# Sheet2.net
KiCad netlist of a schematic drawn in Altium Designer
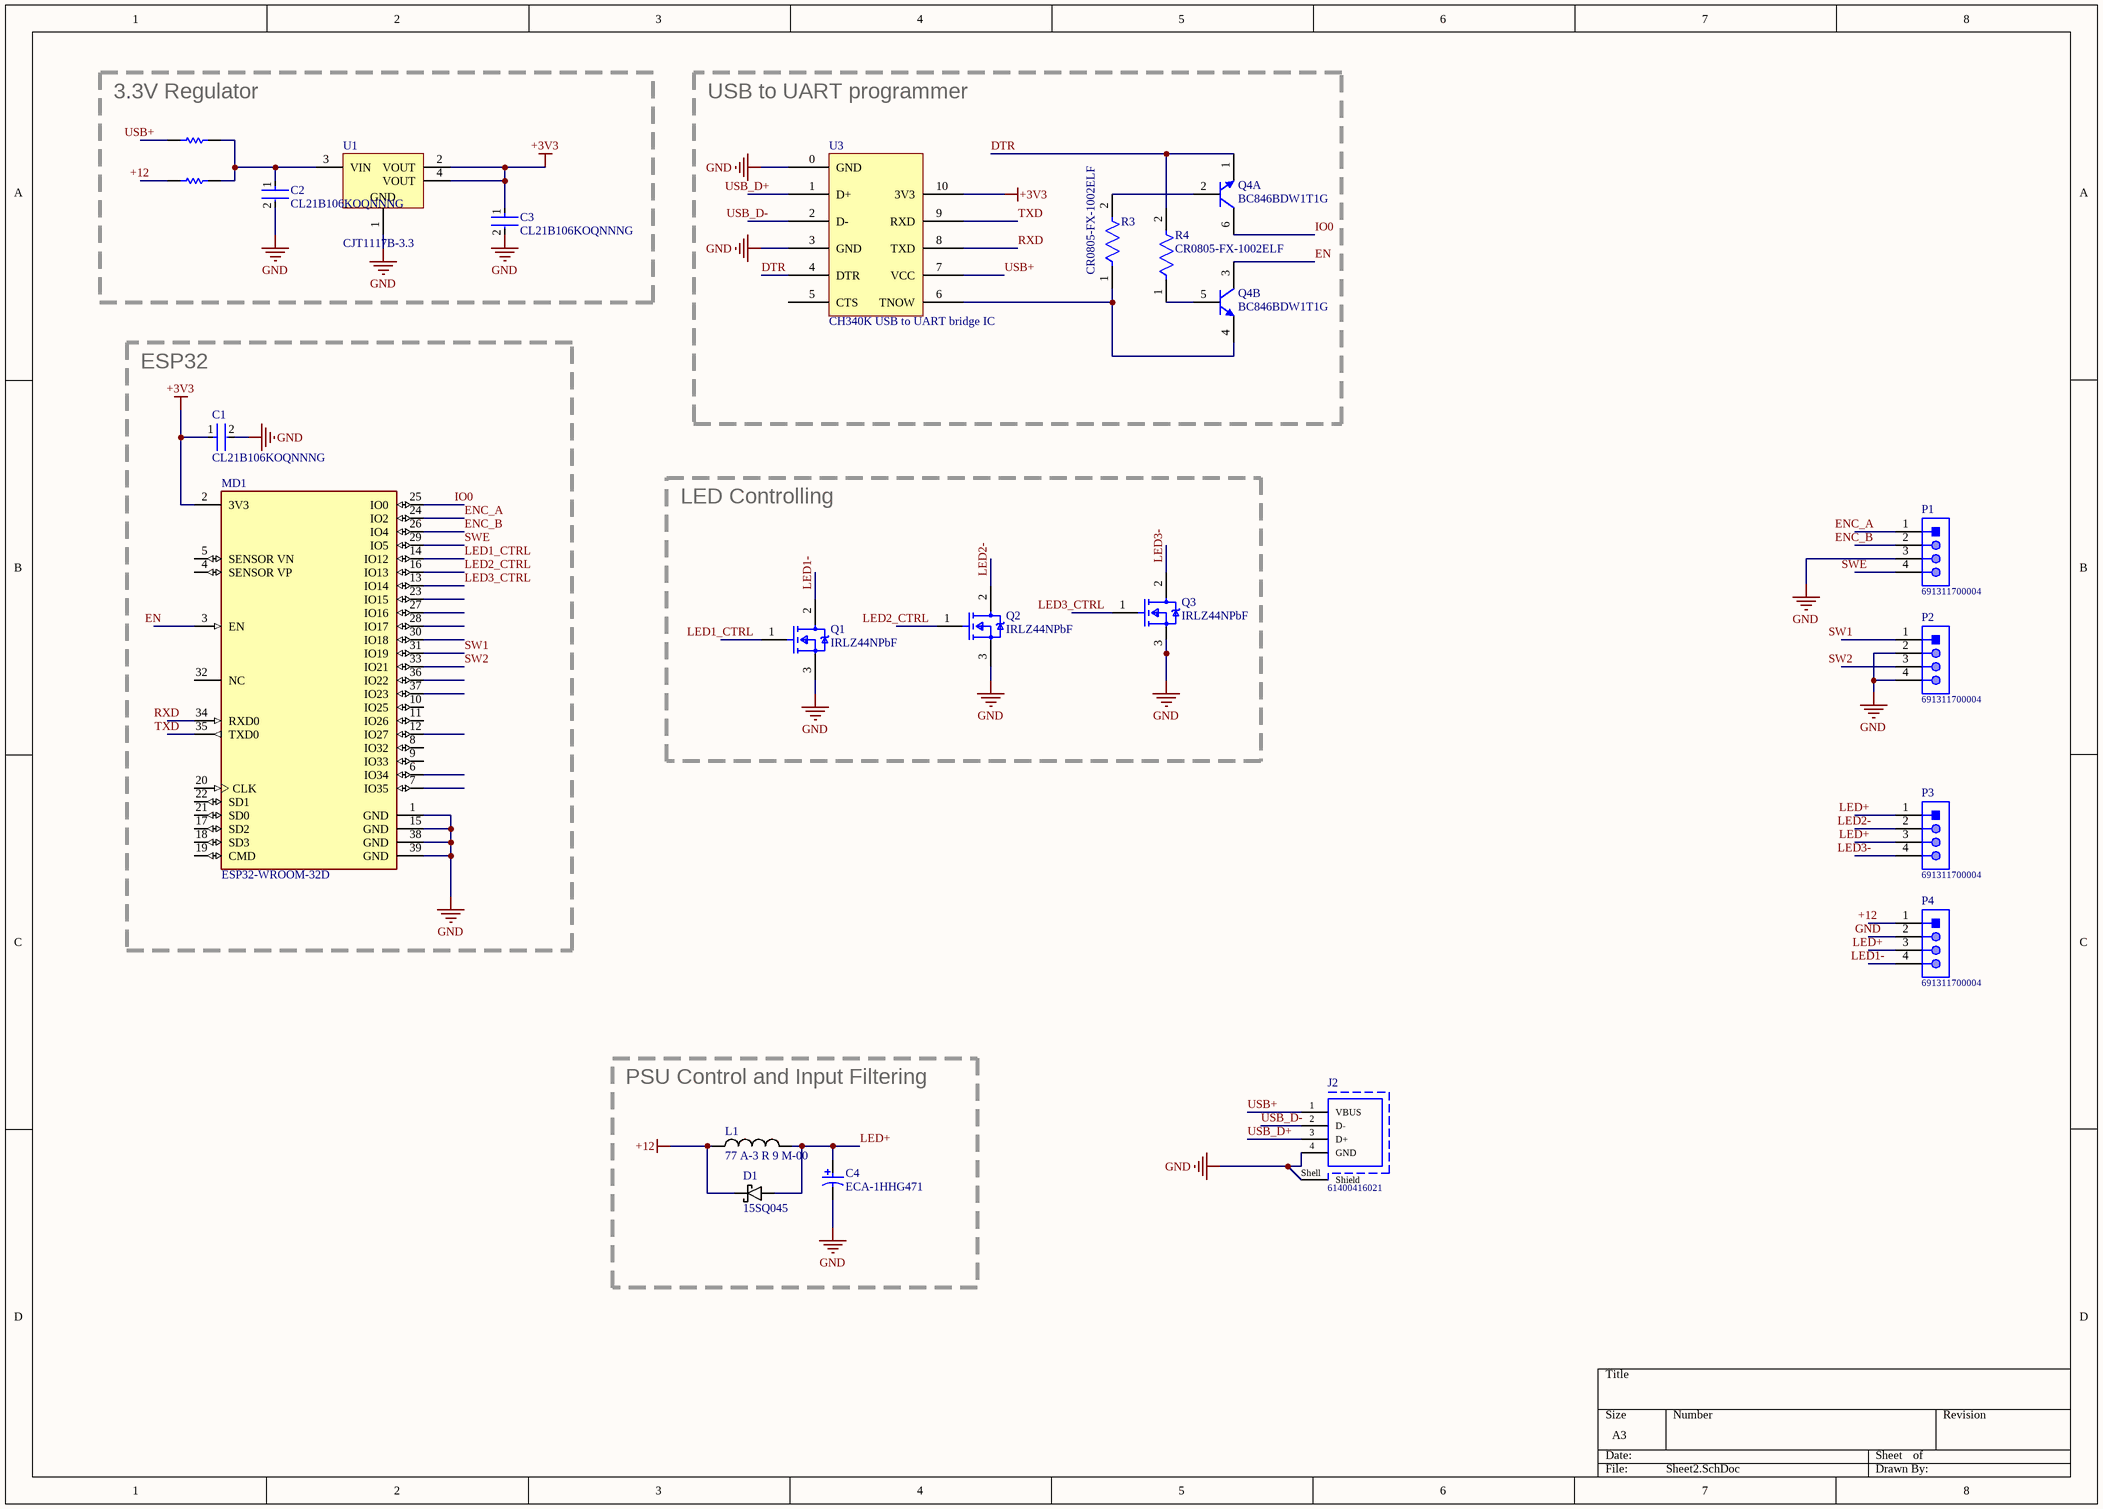
[diagram p0: Sheet2.SchDoc]

(export (version "E")
  (design (tool "Eeschema 10.0.6"))
  (components
    (comp (ref "C1")
      (value "CL21B106KOQNNNG")
      (footprint "FP-CL21B106KOQNNNG-MFG")
      (description "CAP CER 10UF 16V X7R 0805")
      (fields
        (field (name "TOLERANCE") "10%")
        (field (name "OCTOPART") "https://octopart.com/cl21b106koqnnng-samsung-19995691")
      )
      (libsource (lib "Altium Content Vault") (part "b4654b650e69147ec39a6b967a45e02"))
    )
    (comp (ref "C2")
      (value "CL21B106KOQNNNG")
      (footprint "FP-CL21B106KOQNNNG-MFG")
      (description "CAP CER 10UF 16V X7R 0805")
      (fields
        (field (name "TOLERANCE") "10%")
        (field (name "OCTOPART") "https://octopart.com/cl21b106koqnnng-samsung-19995691")
      )
      (libsource (lib "Altium Content Vault") (part "b4654b650e69147ec39a6b967a45e02"))
    )
    (comp (ref "C3")
      (value "CL21B106KOQNNNG")
      (footprint "FP-CL21B106KOQNNNG-MFG")
      (description "CAP CER 10UF 16V X7R 0805")
      (fields
        (field (name "TOLERANCE") "10%")
        (field (name "OCTOPART") "https://octopart.com/cl21b106koqnnng-samsung-19995691")
      )
      (libsource (lib "Altium Content Vault") (part "b4654b650e69147ec39a6b967a45e02"))
    )
    (comp (ref "C4")
      (value "ECA-1HHG471")
      (footprint "PNSC-CAP-10x20-P2")
      (description "Aluminum Electrolytic Capacitor, 470 uF, +/- 20%, 50 V, -55 to 105 degC, 2-Pin THD, RoHS, Bulk")
      (fields (field (name "MANUFACTURER") "Panasonic"))
      (libsource (lib "Altium Content Vault") (part "CAP-P-2"))
    )
    (comp (ref "D1")
      (value "15SQ045")
      (footprint "Shottky Diode")
      (description "Diotec 15SQ045")
      (fields (field (name "VOLTAGE") "45V"))
      (libsource (lib "Schlib1") (part "15SQ045"))
    )
    (comp (ref "J2")
      (value "61400416021")
      (footprint "61400416021")
      (description "USB 2.0 Type A Receptacle WR-COM, Horizontal, THT")
      (fields (field (name "MANUFACTURER") "Wurth Elektronik") (field (name "PUBLISHER") "WurthElektronik"))
      (libsource (lib "Altium Content Vault") (part "WE-USB-4-1SHLD"))
    )
    (comp (ref "L1")
      (value "77 A-3 R 9 M-00")
      (footprint "FIlter Inductor")
      (description "Fastron 77 A-3 R 9 M-00")
      (fields (field (name "TOLERANCE") "+-20%"))
      (libsource (lib "Schlib1") (part "77 A-3 R 9 M-00"))
    )
    (comp (ref "MD1")
      (value "ESP32-WROOM-32D")
      (footprint "FP-ESP32-WROOM-32D-MFG")
      (description "WIFI MODULE 32MBITS SPI FLASH")
      (fields
        (field (name "OCTOPART") "https://octopart.com/esp32-wroom-32d-espressif+systems-91040050")
        (field (name "MANUFACTURER") "Espressif Systems")
      )
      (libsource (lib "Altium Content Vault") (part "a031a76f8c27026a7a7f4657ff233a3"))
    )
    (comp (ref "P1")
      (value "691311700004")
      (footprint "691311700004")
      (description "Serie 3117 - 5.00mm Open Vertical PCB Header WR-TBL, 4 pin, LCSC: DB128V-5.08-4P-GN-S")
      (fields (field (name "MANUFACTURER") "Wurth Elektronik") (field (name "PUBLISHER") "WurthElektronik"))
      (libsource (lib "Altium Content Vault") (part "WE-CN-1P-M-R4"))
    )
    (comp (ref "P2")
      (value "691311700004")
      (footprint "691311700004")
      (description "Serie 3117 - 5.00mm Open Vertical PCB Header WR-TBL, 4 pin, LCSC: DB128V-5.08-4P-GN-S")
      (fields (field (name "MANUFACTURER") "Wurth Elektronik") (field (name "PUBLISHER") "WurthElektronik"))
      (libsource (lib "Altium Content Vault") (part "WE-CN-1P-M-R4"))
    )
    (comp (ref "P3")
      (value "691311700004")
      (footprint "691311700004")
      (description "Serie 3117 - 5.00mm Open Vertical PCB Header WR-TBL, 4 pin, LCSC: DB128V-5.08-4P-GN-S")
      (fields (field (name "MANUFACTURER") "Wurth Elektronik") (field (name "PUBLISHER") "WurthElektronik"))
      (libsource (lib "Altium Content Vault") (part "WE-CN-1P-M-R4"))
    )
    (comp (ref "P4")
      (value "691311700004")
      (footprint "691311700004")
      (description "Serie 3117 - 5.00mm Open Vertical PCB Header WR-TBL, 4 pin, LCSC: DB128V-5.08-4P-GN-S")
      (fields (field (name "MANUFACTURER") "Wurth Elektronik") (field (name "PUBLISHER") "WurthElektronik"))
      (libsource (lib "Altium Content Vault") (part "WE-CN-1P-M-R4"))
    )
    (comp (ref "Q1")
      (value "IRLZ44NPbF")
      (footprint "FP-PG-TO220-3-MFG")
      (description "MOSFET N-CH 55V 47A TO220AB")
      (libsource (lib "Altium Content Vault") (part "b09f7f152735e370c1ea22a33fa83d6"))
    )
    (comp (ref "Q2")
      (value "IRLZ44NPbF")
      (footprint "FP-PG-TO220-3-MFG")
      (description "MOSFET N-CH 55V 47A TO220AB")
      (libsource (lib "Altium Content Vault") (part "b09f7f152735e370c1ea22a33fa83d6"))
    )
    (comp (ref "Q3")
      (value "IRLZ44NPbF")
      (footprint "FP-PG-TO220-3-MFG")
      (description "MOSFET N-CH 55V 47A TO220AB")
      (libsource (lib "Altium Content Vault") (part "b09f7f152735e370c1ea22a33fa83d6"))
    )
    (comp (ref "Q4")
      (value "BC846BDW1T1G")
      (footprint "ONSC-SOT-363-6-419B-02_W_V")
      (description "Dual General Purpose Transistors, NPN, 6-Pin SOT-363, Pb-Free, Tape and Reel")
      (fields (field (name "MANUFACTURER") "On Semiconductor"))
      (libsource (lib "Altium Content Vault") (part "ONSC-NPN_NPN-6_F"))
    )
    (comp (ref "R1")
      (value "RC0603JR-070RL")
      (footprint "RESC1608X55X25ML10T15")
      (description "Chip Resistor, 0 Ohm, +/- 5%, 0.1 W, -55 to 155 degC, 0603 (1608 Metric), RoHS, Tape and Reel")
      (fields (field (name "TOLERANCE") "5%") (field (name "MANUFACTURER") "Yageo"))
      (libsource (lib "Altium Content Vault") (part "RES-2"))
    )
    (comp (ref "R2")
      (value "RC0603JR-070RL")
      (footprint "RESC1608X55X25ML10T15")
      (description "Chip Resistor, 0 Ohm, +/- 5%, 0.1 W, -55 to 155 degC, 0603 (1608 Metric), RoHS, Tape and Reel")
      (fields (field (name "TOLERANCE") "5%") (field (name "MANUFACTURER") "Yageo"))
      (libsource (lib "Altium Content Vault") (part "RES-2"))
    )
    (comp (ref "R3")
      (value "CR0805-FX-1002ELF")
      (footprint "FP-CR0805-IPC_A")
      (description "Thick Film Chip Resistors 0805 10kΩ 0.125W 1% 100ppm/°C")
      (fields (field (name "TOLERANCE") "1%"))
      (libsource (lib "Altium Content Vault") (part "1029c3af85768c4190bb7ad29bc67b5"))
    )
    (comp (ref "R4")
      (value "CR0805-FX-1002ELF")
      (footprint "FP-CR0805-IPC_A")
      (description "Thick Film Chip Resistors 0805 10kΩ 0.125W 1% 100ppm/°C")
      (fields (field (name "TOLERANCE") "1%"))
      (libsource (lib "Altium Content Vault") (part "1029c3af85768c4190bb7ad29bc67b5"))
    )
    (comp (ref "U1")
      (value "CJT1117B-3.3")
      (footprint "DCY0004A_L")
      (libsource (lib "Altium Content Vault") (part "TI-REG1117-XXXX"))
    )
    (comp (ref "U3")
      (value "CH340K USB to UART bridge IC")
      (footprint "CH340K footprint")
      (libsource (lib "Schlib1") (part "CH340K"))
    )
  )
  (nets
    (net (code "1") (name "+3V3") (class "Default")
      (node (ref "C1") (pin "1") (pinfunction "1_1") (pintype "passive"))
      (node (ref "C3") (pin "1") (pinfunction "1_1") (pintype "passive"))
      (node (ref "MD1") (pin "2") (pinfunction "3V3_2") (pintype "power_in"))
      (node (ref "U1") (pin "2") (pinfunction "VOUT_2") (pintype "power_in"))
      (node (ref "U1") (pin "4") (pinfunction "VOUT_4") (pintype "power_in"))
      (node (ref "U3") (pin "10") (pinfunction "3V3_10") (pintype "passive"))
    )
    (net (code "2") (name "+12") (class "Default")
      (node (ref "D1") (pin "2") (pinfunction "2_2") (pintype "passive"))
      (node (ref "L1") (pin "1") (pinfunction "1_1") (pintype "passive"))
      (node (ref "P4") (pin "1") (pinfunction "1_1") (pintype "passive"))
      (node (ref "R2") (pin "1") (pinfunction "1_1") (pintype "passive"))
    )
    (net (code "3") (name "/DTR") (class "Default")
      (node (ref "Q4") (pin "1") (pinfunction "E_1") (pintype "passive"))
      (node (ref "R4") (pin "2") (pinfunction "2_2") (pintype "passive"))
      (node (ref "U3") (pin "4") (pinfunction "DTR_4") (pintype "passive"))
    )
    (net (code "4") (name "/EN") (class "Default")
      (node (ref "MD1") (pin "3") (pinfunction "EN_3") (pintype "input"))
      (node (ref "Q4") (pin "3") (pinfunction "C_3") (pintype "passive"))
    )
    (net (code "5") (name "/ENC_A") (class "Default")
      (node (ref "MD1") (pin "24") (pinfunction "IO2_24") (pintype "bidirectional"))
      (node (ref "P1") (pin "1") (pinfunction "1_1") (pintype "passive"))
    )
    (net (code "6") (name "/ENC_B") (class "Default")
      (node (ref "MD1") (pin "26") (pinfunction "IO4_26") (pintype "bidirectional"))
      (node (ref "P1") (pin "2") (pinfunction "2_2") (pintype "passive"))
    )
    (net (code "7") (name "/IO0") (class "Default")
      (node (ref "MD1") (pin "25") (pinfunction "IO0_25") (pintype "bidirectional"))
      (node (ref "Q4") (pin "6") (pinfunction "C_6") (pintype "passive"))
    )
    (net (code "8") (name "/LED+") (class "Default")
      (node (ref "C4") (pin "1") (pinfunction "1_1") (pintype "passive"))
      (node (ref "D1") (pin "1") (pinfunction "1_1") (pintype "passive"))
      (node (ref "L1") (pin "2") (pinfunction "2_2") (pintype "passive"))
      (node (ref "P3") (pin "1") (pinfunction "1_1") (pintype "passive"))
      (node (ref "P3") (pin "3") (pinfunction "3_3") (pintype "passive"))
      (node (ref "P4") (pin "3") (pinfunction "3_3") (pintype "passive"))
    )
    (net (code "9") (name "/LED1-") (class "Default")
      (node (ref "P4") (pin "4") (pinfunction "4_4") (pintype "passive"))
      (node (ref "Q1") (pin "2") (pinfunction "D_2") (pintype "passive"))
    )
    (net (code "10") (name "/LED1_CTRL") (class "Default")
      (node (ref "MD1") (pin "14") (pinfunction "IO12_14") (pintype "bidirectional"))
      (node (ref "Q1") (pin "1") (pinfunction "G_1") (pintype "passive"))
    )
    (net (code "11") (name "/LED2-") (class "Default")
      (node (ref "P3") (pin "2") (pinfunction "2_2") (pintype "passive"))
      (node (ref "Q2") (pin "2") (pinfunction "D_2") (pintype "passive"))
    )
    (net (code "12") (name "/LED2_CTRL") (class "Default")
      (node (ref "MD1") (pin "16") (pinfunction "IO13_16") (pintype "bidirectional"))
      (node (ref "Q2") (pin "1") (pinfunction "G_1") (pintype "passive"))
    )
    (net (code "13") (name "/LED3-") (class "Default")
      (node (ref "P3") (pin "4") (pinfunction "4_4") (pintype "passive"))
      (node (ref "Q3") (pin "2") (pinfunction "D_2") (pintype "passive"))
    )
    (net (code "14") (name "/LED3_CTRL") (class "Default")
      (node (ref "MD1") (pin "13") (pinfunction "IO14_13") (pintype "bidirectional"))
      (node (ref "Q3") (pin "1") (pinfunction "G_1") (pintype "passive"))
    )
    (net (code "15") (name "/RXD") (class "Default")
      (node (ref "MD1") (pin "34") (pinfunction "RXD0_34") (pintype "input"))
      (node (ref "U3") (pin "8") (pinfunction "TXD_8") (pintype "passive"))
    )
    (net (code "16") (name "/SW1") (class "Default")
      (node (ref "MD1") (pin "31") (pinfunction "IO19_31") (pintype "bidirectional"))
      (node (ref "P2") (pin "1") (pinfunction "1_1") (pintype "passive"))
    )
    (net (code "17") (name "/SW2") (class "Default")
      (node (ref "MD1") (pin "33") (pinfunction "IO21_33") (pintype "bidirectional"))
      (node (ref "P2") (pin "3") (pinfunction "3_3") (pintype "passive"))
    )
    (net (code "18") (name "/SWE") (class "Default")
      (node (ref "MD1") (pin "29") (pinfunction "IO5_29") (pintype "bidirectional"))
      (node (ref "P1") (pin "4") (pinfunction "4_4") (pintype "passive"))
    )
    (net (code "19") (name "/TXD") (class "Default")
      (node (ref "MD1") (pin "35") (pinfunction "TXD0_35") (pintype "output"))
      (node (ref "U3") (pin "9") (pinfunction "RXD_9") (pintype "passive"))
    )
    (net (code "20") (name "/USB+") (class "Default")
      (node (ref "J2") (pin "1") (pinfunction "VBUS_1") (pintype "passive"))
      (node (ref "R1") (pin "1") (pinfunction "1_1") (pintype "passive"))
      (node (ref "U3") (pin "7") (pinfunction "VCC_7") (pintype "passive"))
    )
    (net (code "21") (name "/USB_D+") (class "Default")
      (node (ref "J2") (pin "3") (pinfunction "D+_3") (pintype "passive"))
      (node (ref "U3") (pin "1") (pinfunction "D+_1") (pintype "passive"))
    )
    (net (code "22") (name "/USB_D-") (class "Default")
      (node (ref "J2") (pin "2") (pinfunction "D-_2") (pintype "passive"))
      (node (ref "U3") (pin "2") (pinfunction "D-_2") (pintype "passive"))
    )
    (net (code "23") (name "GND") (class "Default")
      (node (ref "C1") (pin "2") (pinfunction "2_2") (pintype "passive"))
      (node (ref "C2") (pin "2") (pinfunction "2_2") (pintype "passive"))
      (node (ref "C3") (pin "2") (pinfunction "2_2") (pintype "passive"))
      (node (ref "C4") (pin "2") (pinfunction "2_2") (pintype "passive"))
      (node (ref "J2") (pin "4") (pinfunction "GND_4") (pintype "passive"))
      (node (ref "J2") (pin "Shell") (pinfunction "Shield_Shell") (pintype "passive"))
      (node (ref "MD1") (pin "1") (pinfunction "GND_1") (pintype "power_in"))
      (node (ref "MD1") (pin "15") (pinfunction "GND_15") (pintype "power_in"))
      (node (ref "MD1") (pin "38") (pinfunction "GND_38") (pintype "power_in"))
      (node (ref "MD1") (pin "39") (pinfunction "GND_39") (pintype "power_in"))
      (node (ref "P1") (pin "3") (pinfunction "3_3") (pintype "passive"))
      (node (ref "P2") (pin "2") (pinfunction "2_2") (pintype "passive"))
      (node (ref "P2") (pin "4") (pinfunction "4_4") (pintype "passive"))
      (node (ref "P4") (pin "2") (pinfunction "2_2") (pintype "passive"))
      (node (ref "Q1") (pin "3") (pinfunction "S_3") (pintype "passive"))
      (node (ref "Q2") (pin "3") (pinfunction "S_3") (pintype "passive"))
      (node (ref "Q3") (pin "3") (pinfunction "S_3") (pintype "passive"))
      (node (ref "U1") (pin "1") (pinfunction "GND_1") (pintype "power_in"))
      (node (ref "U3") (pin "0") (pinfunction "GND_0") (pintype "passive"))
      (node (ref "U3") (pin "3") (pinfunction "GND_3") (pintype "passive"))
    )
    (net (code "24") (name "Net-(Q4A-B)") (class "Default")
      (node (ref "Q4") (pin "2") (pinfunction "B_2") (pintype "passive"))
      (node (ref "R3") (pin "2") (pinfunction "2_2") (pintype "passive"))
    )
    (net (code "25") (name "Net-(Q4B-B)") (class "Default")
      (node (ref "Q4") (pin "5") (pinfunction "B_5") (pintype "passive"))
      (node (ref "R4") (pin "1") (pinfunction "1_1") (pintype "passive"))
    )
    (net (code "26") (name "Net-(Q4B-E)") (class "Default")
      (node (ref "Q4") (pin "4") (pinfunction "E_4") (pintype "passive"))
      (node (ref "R3") (pin "1") (pinfunction "1_1") (pintype "passive"))
      (node (ref "U3") (pin "6") (pinfunction "TNOW_6") (pintype "passive"))
    )
    (net (code "27") (name "Net-(U1-VIN)") (class "Default")
      (node (ref "C2") (pin "1") (pinfunction "1_1") (pintype "passive"))
      (node (ref "R1") (pin "2") (pinfunction "2_2") (pintype "passive"))
      (node (ref "R2") (pin "2") (pinfunction "2_2") (pintype "passive"))
      (node (ref "U1") (pin "3") (pinfunction "VIN_3") (pintype "power_in"))
    )
    (net (code "28") (name "unconnected-(MD1-CLK-Pad20)") (class "Default")
      (node (ref "MD1") (pin "20") (pinfunction "CLK_20") (pintype "input"))
    )
    (net (code "29") (name "unconnected-(MD1-CMD-Pad19)") (class "Default")
      (node (ref "MD1") (pin "19") (pinfunction "CMD_19") (pintype "bidirectional"))
    )
    (net (code "30") (name "unconnected-(MD1-IO15-Pad23)") (class "Default")
      (node (ref "MD1") (pin "23") (pinfunction "IO15_23") (pintype "bidirectional"))
    )
    (net (code "31") (name "unconnected-(MD1-IO16-Pad27)") (class "Default")
      (node (ref "MD1") (pin "27") (pinfunction "IO16_27") (pintype "bidirectional"))
    )
    (net (code "32") (name "unconnected-(MD1-IO17-Pad28)") (class "Default")
      (node (ref "MD1") (pin "28") (pinfunction "IO17_28") (pintype "bidirectional"))
    )
    (net (code "33") (name "unconnected-(MD1-IO18-Pad30)") (class "Default")
      (node (ref "MD1") (pin "30") (pinfunction "IO18_30") (pintype "bidirectional"))
    )
    (net (code "34") (name "unconnected-(MD1-IO22-Pad36)") (class "Default")
      (node (ref "MD1") (pin "36") (pinfunction "IO22_36") (pintype "bidirectional"))
    )
    (net (code "35") (name "unconnected-(MD1-IO23-Pad37)") (class "Default")
      (node (ref "MD1") (pin "37") (pinfunction "IO23_37") (pintype "bidirectional"))
    )
    (net (code "36") (name "unconnected-(MD1-IO25-Pad10)") (class "Default")
      (node (ref "MD1") (pin "10") (pinfunction "IO25_10") (pintype "bidirectional"))
    )
    (net (code "37") (name "unconnected-(MD1-IO26-Pad11)") (class "Default")
      (node (ref "MD1") (pin "11") (pinfunction "IO26_11") (pintype "bidirectional"))
    )
    (net (code "38") (name "unconnected-(MD1-IO27-Pad12)") (class "Default")
      (node (ref "MD1") (pin "12") (pinfunction "IO27_12") (pintype "bidirectional"))
    )
    (net (code "39") (name "unconnected-(MD1-IO32-Pad8)") (class "Default")
      (node (ref "MD1") (pin "8") (pinfunction "IO32_8") (pintype "bidirectional"))
    )
    (net (code "40") (name "unconnected-(MD1-IO33-Pad9)") (class "Default")
      (node (ref "MD1") (pin "9") (pinfunction "IO33_9") (pintype "bidirectional"))
    )
    (net (code "41") (name "unconnected-(MD1-IO34-Pad6)") (class "Default")
      (node (ref "MD1") (pin "6") (pinfunction "IO34_6") (pintype "bidirectional"))
    )
    (net (code "42") (name "unconnected-(MD1-IO35-Pad7)") (class "Default")
      (node (ref "MD1") (pin "7") (pinfunction "IO35_7") (pintype "bidirectional"))
    )
    (net (code "43") (name "unconnected-(MD1-NC-Pad32)") (class "Default")
      (node (ref "MD1") (pin "32") (pinfunction "NC_32") (pintype "passive"))
    )
    (net (code "44") (name "unconnected-(MD1-SD0-Pad21)") (class "Default")
      (node (ref "MD1") (pin "21") (pinfunction "SD0_21") (pintype "bidirectional"))
    )
    (net (code "45") (name "unconnected-(MD1-SD1-Pad22)") (class "Default")
      (node (ref "MD1") (pin "22") (pinfunction "SD1_22") (pintype "bidirectional"))
    )
    (net (code "46") (name "unconnected-(MD1-SD2-Pad17)") (class "Default")
      (node (ref "MD1") (pin "17") (pinfunction "SD2_17") (pintype "bidirectional"))
    )
    (net (code "47") (name "unconnected-(MD1-SD3-Pad18)") (class "Default")
      (node (ref "MD1") (pin "18") (pinfunction "SD3_18") (pintype "bidirectional"))
    )
    (net (code "48") (name "unconnected-(MD1-SENSOR_VN-Pad5)") (class "Default")
      (node (ref "MD1") (pin "5") (pinfunction "SENSOR_VN_5") (pintype "bidirectional"))
    )
    (net (code "49") (name "unconnected-(MD1-SENSOR_VP-Pad4)") (class "Default")
      (node (ref "MD1") (pin "4") (pinfunction "SENSOR_VP_4") (pintype "bidirectional"))
    )
    (net (code "50") (name "unconnected-(U3-CTS-Pad5)") (class "Default")
      (node (ref "U3") (pin "5") (pinfunction "CTS_5") (pintype "passive"))
    )
  )
)
